# schematic.net
KiCad netlist of a schematic drawn in EAGLE
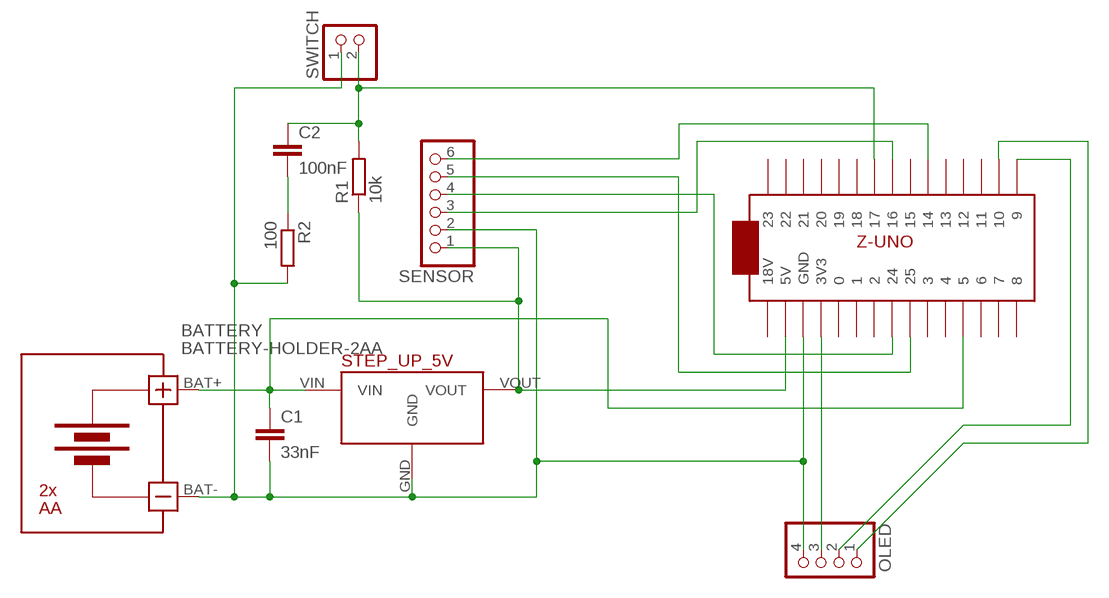
[diagram p0: schematic, sheet 1]

(export (version "E")
  (design (tool "Eeschema 10.0.6"))
  (components
    (comp (ref "BATTERY")
      (value "BATTERY-HOLDER-2AA")
      (footprint "eagle-import:BATTERY-HOLDER-2AA")
      (libsource (lib "eagle-import") (part "BATTERY-HOLDER-2AA"))
    )
    (comp (ref "C1")
      (value "33nF")
      (footprint "eagle-import:C025-024X044")
      (libsource (lib "eagle-import") (part "C-EU025-024X044"))
    )
    (comp (ref "C2")
      (value "100nF")
      (footprint "eagle-import:C025-024X044")
      (libsource (lib "eagle-import") (part "C-EU025-024X044"))
    )
    (comp (ref "OLED")
      (value "PINHD-1X4")
      (footprint "eagle-import:1X04")
      (libsource (lib "eagle-import") (part "PINHD-1X4"))
    )
    (comp (ref "R1")
      (value "10k")
      (footprint "eagle-import:0204_7")
      (libsource (lib "eagle-import") (part "R-EU_0204/7"))
    )
    (comp (ref "R2")
      (value "100")
      (footprint "eagle-import:0204_7")
      (libsource (lib "eagle-import") (part "R-EU_0204/7"))
    )
    (comp (ref "SENSOR")
      (value "PINHD-1X6")
      (footprint "eagle-import:1X06")
      (libsource (lib "eagle-import") (part "PINHD-1X6"))
    )
    (comp (ref "STEP_UP_5V")
      (value "5V_VOLTAGE_REGULATOR")
      (footprint "eagle-import:5V_VOLTAGE_REGULATOR")
      (libsource (lib "eagle-import") (part "5V_VOLTAGE_REGULATOR"))
    )
    (comp (ref "SWITCH")
      (value "PINHD-1X2")
      (footprint "eagle-import:1X02")
      (libsource (lib "eagle-import") (part "PINHD-1X2"))
    )
    (comp (ref "ZUNO")
      (value "ZUNO")
      (footprint "eagle-import:ZUNO")
      (libsource (lib "eagle-import") (part "ZUNO"))
    )
  )
  (nets
    (net (code "1") (name "Net-(C2-Pad2)") (class "Default")
      (node (ref "C2") (pin "2") (pinfunction "2_2") (pintype "passive"))
      (node (ref "R2") (pin "1") (pinfunction "1_1") (pintype "passive"))
    )
    (net (code "2") (name "Net-(ZUNO-3V3)") (class "Default")
      (node (ref "OLED") (pin "3") (pinfunction "3_3") (pintype "passive"))
      (node (ref "ZUNO") (pin "P$4") (pinfunction "3V3_P$4") (pintype "bidirectional"))
    )
    (net (code "3") (name "Net-(ZUNO-5)") (class "Default")
      (node (ref "BATTERY") (pin "BAT+") (pinfunction "BAT+_BAT+") (pintype "power_in"))
      (node (ref "C1") (pin "1") (pinfunction "1_1") (pintype "passive"))
      (node (ref "STEP_UP_5V") (pin "VIN") (pinfunction "VIN_VIN") (pintype "bidirectional"))
      (node (ref "ZUNO") (pin "P$12") (pinfunction "5_P$12") (pintype "bidirectional"))
    )
    (net (code "4") (name "Net-(ZUNO-5V)") (class "Default")
      (node (ref "R1") (pin "1") (pinfunction "1_1") (pintype "passive"))
      (node (ref "SENSOR") (pin "1") (pinfunction "1_1") (pintype "passive"))
      (node (ref "STEP_UP_5V") (pin "VOUT") (pinfunction "VOUT_VOUT") (pintype "bidirectional"))
      (node (ref "ZUNO") (pin "P$2") (pinfunction "5V_P$2") (pintype "bidirectional"))
    )
    (net (code "5") (name "Net-(ZUNO-9)") (class "Default")
      (node (ref "OLED") (pin "2") (pinfunction "2_2") (pintype "passive"))
      (node (ref "ZUNO") (pin "P$16") (pinfunction "9_P$16") (pintype "bidirectional"))
    )
    (net (code "6") (name "Net-(ZUNO-10)") (class "Default")
      (node (ref "OLED") (pin "1") (pinfunction "1_1") (pintype "passive"))
      (node (ref "ZUNO") (pin "P$17") (pinfunction "10_P$17") (pintype "bidirectional"))
    )
    (net (code "7") (name "Net-(ZUNO-14)") (class "Default")
      (node (ref "SENSOR") (pin "6") (pinfunction "6_6") (pintype "passive"))
      (node (ref "ZUNO") (pin "P$21") (pinfunction "14_P$21") (pintype "bidirectional"))
    )
    (net (code "8") (name "Net-(ZUNO-16)") (class "Default")
      (node (ref "SENSOR") (pin "3") (pinfunction "3_3") (pintype "passive"))
      (node (ref "ZUNO") (pin "P$23") (pinfunction "16_P$23") (pintype "bidirectional"))
    )
    (net (code "9") (name "Net-(ZUNO-17)") (class "Default")
      (node (ref "C2") (pin "1") (pinfunction "1_1") (pintype "passive"))
      (node (ref "R1") (pin "2") (pinfunction "2_2") (pintype "passive"))
      (node (ref "SWITCH") (pin "2") (pinfunction "2_2") (pintype "passive"))
      (node (ref "ZUNO") (pin "P$24") (pinfunction "17_P$24") (pintype "bidirectional"))
    )
    (net (code "10") (name "Net-(ZUNO-24)") (class "Default")
      (node (ref "SENSOR") (pin "4") (pinfunction "4_4") (pintype "passive"))
      (node (ref "ZUNO") (pin "P$8") (pinfunction "24_P$8") (pintype "bidirectional"))
    )
    (net (code "11") (name "Net-(ZUNO-25)") (class "Default")
      (node (ref "SENSOR") (pin "5") (pinfunction "5_5") (pintype "passive"))
      (node (ref "ZUNO") (pin "P$9") (pinfunction "25_P$9") (pintype "bidirectional"))
    )
    (net (code "12") (name "Net-(ZUNO-GND)") (class "Default")
      (node (ref "BATTERY") (pin "BAT-") (pinfunction "BAT-_BAT-") (pintype "power_in"))
      (node (ref "C1") (pin "2") (pinfunction "2_2") (pintype "passive"))
      (node (ref "OLED") (pin "4") (pinfunction "4_4") (pintype "passive"))
      (node (ref "R2") (pin "2") (pinfunction "2_2") (pintype "passive"))
      (node (ref "SENSOR") (pin "2") (pinfunction "2_2") (pintype "passive"))
      (node (ref "STEP_UP_5V") (pin "GND") (pinfunction "GND_GND") (pintype "bidirectional"))
      (node (ref "SWITCH") (pin "1") (pinfunction "1_1") (pintype "passive"))
      (node (ref "ZUNO") (pin "P$3") (pinfunction "GND_P$3") (pintype "bidirectional"))
    )
    (net (code "13") (name "unconnected-(ZUNO-0-PadP$5)") (class "Default")
      (node (ref "ZUNO") (pin "P$5") (pinfunction "0_P$5") (pintype "bidirectional"))
    )
    (net (code "14") (name "unconnected-(ZUNO-1-PadP$6)") (class "Default")
      (node (ref "ZUNO") (pin "P$6") (pinfunction "1_P$6") (pintype "bidirectional"))
    )
    (net (code "15") (name "unconnected-(ZUNO-2-PadP$7)") (class "Default")
      (node (ref "ZUNO") (pin "P$7") (pinfunction "2_P$7") (pintype "bidirectional"))
    )
    (net (code "16") (name "unconnected-(ZUNO-3-PadP$10)") (class "Default")
      (node (ref "ZUNO") (pin "P$10") (pinfunction "3_P$10") (pintype "bidirectional"))
    )
    (net (code "17") (name "unconnected-(ZUNO-4-PadP$11)") (class "Default")
      (node (ref "ZUNO") (pin "P$11") (pinfunction "4_P$11") (pintype "bidirectional"))
    )
    (net (code "18") (name "unconnected-(ZUNO-6-PadP$13)") (class "Default")
      (node (ref "ZUNO") (pin "P$13") (pinfunction "6_P$13") (pintype "bidirectional"))
    )
    (net (code "19") (name "unconnected-(ZUNO-7-PadP$14)") (class "Default")
      (node (ref "ZUNO") (pin "P$14") (pinfunction "7_P$14") (pintype "bidirectional"))
    )
    (net (code "20") (name "unconnected-(ZUNO-8-PadP$15)") (class "Default")
      (node (ref "ZUNO") (pin "P$15") (pinfunction "8_P$15") (pintype "bidirectional"))
    )
    (net (code "21") (name "unconnected-(ZUNO-11-PadP$18)") (class "Default")
      (node (ref "ZUNO") (pin "P$18") (pinfunction "11_P$18") (pintype "bidirectional"))
    )
    (net (code "22") (name "unconnected-(ZUNO-12-PadP$19)") (class "Default")
      (node (ref "ZUNO") (pin "P$19") (pinfunction "12_P$19") (pintype "bidirectional"))
    )
    (net (code "23") (name "unconnected-(ZUNO-13-PadP$20)") (class "Default")
      (node (ref "ZUNO") (pin "P$20") (pinfunction "13_P$20") (pintype "bidirectional"))
    )
    (net (code "24") (name "unconnected-(ZUNO-15-PadP$22)") (class "Default")
      (node (ref "ZUNO") (pin "P$22") (pinfunction "15_P$22") (pintype "bidirectional"))
    )
    (net (code "25") (name "unconnected-(ZUNO-18-PadP$25)") (class "Default")
      (node (ref "ZUNO") (pin "P$25") (pinfunction "18_P$25") (pintype "bidirectional"))
    )
    (net (code "26") (name "unconnected-(ZUNO-18V-PadP$1)") (class "Default")
      (node (ref "ZUNO") (pin "P$1") (pinfunction "18V_P$1") (pintype "bidirectional"))
    )
    (net (code "27") (name "unconnected-(ZUNO-19-PadP$26)") (class "Default")
      (node (ref "ZUNO") (pin "P$26") (pinfunction "19_P$26") (pintype "bidirectional"))
    )
    (net (code "28") (name "unconnected-(ZUNO-20-PadP$27)") (class "Default")
      (node (ref "ZUNO") (pin "P$27") (pinfunction "20_P$27") (pintype "bidirectional"))
    )
    (net (code "29") (name "unconnected-(ZUNO-21-PadP$28)") (class "Default")
      (node (ref "ZUNO") (pin "P$28") (pinfunction "21_P$28") (pintype "bidirectional"))
    )
    (net (code "30") (name "unconnected-(ZUNO-22-PadP$29)") (class "Default")
      (node (ref "ZUNO") (pin "P$29") (pinfunction "22_P$29") (pintype "bidirectional"))
    )
    (net (code "31") (name "unconnected-(ZUNO-23-PadP$30)") (class "Default")
      (node (ref "ZUNO") (pin "P$30") (pinfunction "23_P$30") (pintype "bidirectional"))
    )
  )
)
